# adb_converter.net
KiCad netlist of a schematic drawn in EAGLE
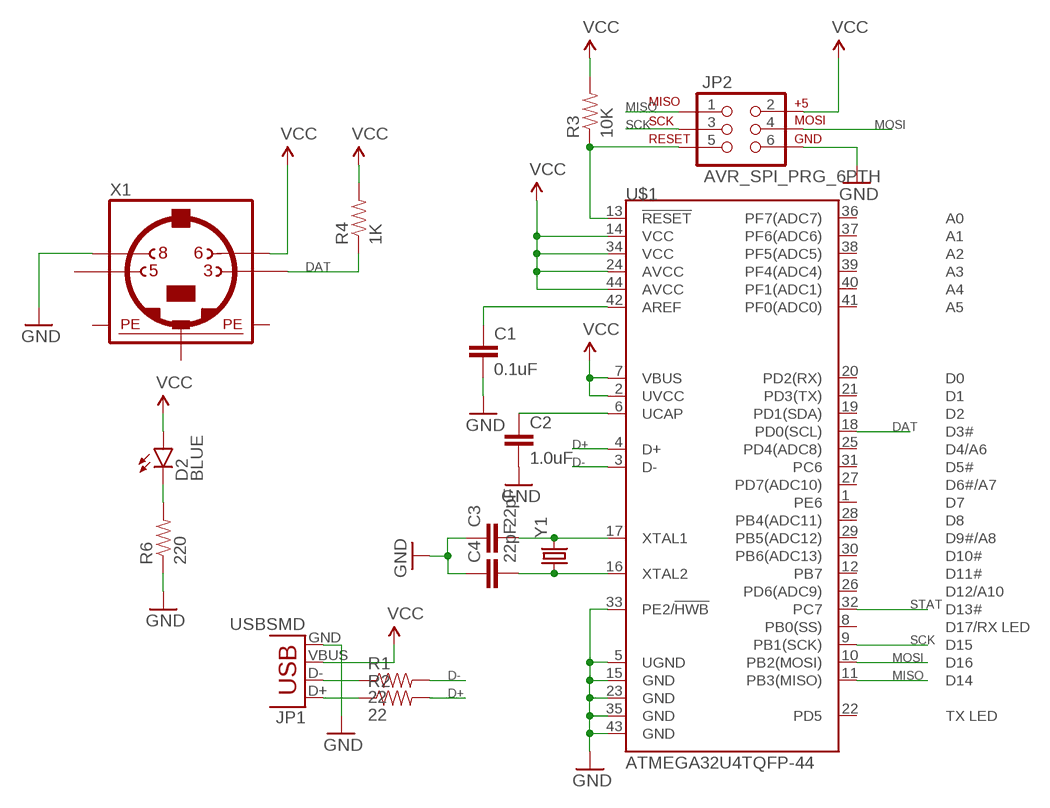
[diagram p0: schematic, sheet 1]

(export (version "E")
  (design (tool "Eeschema 10.0.6"))
  (components
    (comp (ref "C1")
      (value "0.1uF")
      (footprint "eagle-import:0603-CAP")
      (libsource (lib "eagle-import") (part "0.1UF-25V-5%(0603)"))
    )
    (comp (ref "C2")
      (value "1.0uF")
      (footprint "eagle-import:0603-CAP")
      (libsource (lib "eagle-import") (part "1.0UF-16V-10%(0603)"))
    )
    (comp (ref "C3")
      (value "22pF")
      (footprint "eagle-import:0603-CAP")
      (libsource (lib "eagle-import") (part "22PF-50V-5%(0603)"))
    )
    (comp (ref "C4")
      (value "22pF")
      (footprint "eagle-import:0603-CAP")
      (libsource (lib "eagle-import") (part "22PF-50V-5%(0603)"))
    )
    (comp (ref "D2")
      (value "BLUE")
      (footprint "eagle-import:LED-0603")
      (libsource (lib "eagle-import") (part "LED-BLUE0603"))
    )
    (comp (ref "JP1")
      (value "USBSMD")
      (footprint "eagle-import:USB-MINIB")
      (libsource (lib "eagle-import") (part "USBSMD"))
    )
    (comp (ref "JP2")
      (value "AVR_SPI_PRG_6PTH")
      (footprint "eagle-import:2X3")
      (libsource (lib "eagle-import") (part "AVR_SPI_PRG_6PTH"))
    )
    (comp (ref "R1")
      (value "22")
      (footprint "eagle-import:0603-RES")
      (libsource (lib "eagle-import") (part "22OHM1/10W1%(0603)"))
    )
    (comp (ref "R2")
      (value "22")
      (footprint "eagle-import:0603-RES")
      (libsource (lib "eagle-import") (part "22OHM1/10W1%(0603)"))
    )
    (comp (ref "R3")
      (value "10K")
      (footprint "eagle-import:0603-RES")
      (libsource (lib "eagle-import") (part "10KOHM-1/10W-1%(0603)0603"))
    )
    (comp (ref "R4")
      (value "1K")
      (footprint "eagle-import:0603-RES")
      (libsource (lib "eagle-import") (part "1KOHM-1/10W-1%(0603)"))
    )
    (comp (ref "R6")
      (value "220")
      (footprint "eagle-import:0603-RES")
      (libsource (lib "eagle-import") (part "220OHM-1/10W-1%(0603)"))
    )
    (comp (ref "U$1")
      (value "ATMEGA32U4TQFP-44")
      (footprint "eagle-import:TQFP44")
      (libsource (lib "eagle-import") (part "ATMEGA32U4TQFP-44"))
    )
    (comp (ref "X1")
      (value "MINI_DIN_4")
      (footprint "eagle-import:M_DIN4")
      (libsource (lib "eagle-import") (part "MINI_DIN_4"))
    )
    (comp (ref "Y1")
      (value "CRYSTALHC49US")
      (footprint "eagle-import:HC49US")
      (libsource (lib "eagle-import") (part "CRYSTALHC49US"))
    )
  )
  (nets
    (net (code "1") (name "/D+") (class "Default")
      (node (ref "R2") (pin "2") (pinfunction "2_2") (pintype "passive"))
      (node (ref "U$1") (pin "4") (pinfunction "D+_4") (pintype "bidirectional"))
    )
    (net (code "2") (name "/D-") (class "Default")
      (node (ref "R1") (pin "2") (pinfunction "2_2") (pintype "passive"))
      (node (ref "U$1") (pin "3") (pinfunction "D-_3") (pintype "bidirectional"))
    )
    (net (code "3") (name "/DAT") (class "Default")
      (node (ref "R4") (pin "1") (pinfunction "1_1") (pintype "passive"))
      (node (ref "U$1") (pin "18") (pinfunction "PD0(SCL)_18") (pintype "bidirectional"))
      (node (ref "X1") (pin "3") (pinfunction "3_3") (pintype "passive"))
    )
    (net (code "4") (name "/MISO") (class "Default")
      (node (ref "JP2") (pin "1") (pinfunction "1_1") (pintype "passive"))
      (node (ref "U$1") (pin "11") (pinfunction "PB3(MISO)_11") (pintype "bidirectional"))
    )
    (net (code "5") (name "/MOSI") (class "Default")
      (node (ref "JP2") (pin "4") (pinfunction "4_4") (pintype "passive"))
      (node (ref "U$1") (pin "10") (pinfunction "PB2(MOSI)_10") (pintype "bidirectional"))
    )
    (net (code "6") (name "/PE1") (class "Default")
      (node (ref "X1") (pin "SH1") (pinfunction "PE1_SH1") (pintype "power_in"))
    )
    (net (code "7") (name "/PE2") (class "Default")
      (node (ref "X1") (pin "SH2") (pinfunction "PE2_SH2") (pintype "power_in"))
    )
    (net (code "8") (name "/PE3") (class "Default")
      (node (ref "X1") (pin "SH3") (pinfunction "PE3_SH3") (pintype "power_in"))
    )
    (net (code "9") (name "/SCK") (class "Default")
      (node (ref "JP2") (pin "3") (pinfunction "3_3") (pintype "passive"))
      (node (ref "U$1") (pin "9") (pinfunction "PB1(SCK)_9") (pintype "bidirectional"))
    )
    (net (code "10") (name "/STAT") (class "Default")
      (node (ref "U$1") (pin "32") (pinfunction "PC7_32") (pintype "bidirectional"))
    )
    (net (code "11") (name "GND") (class "Default")
      (node (ref "C1") (pin "2") (pinfunction "2_2") (pintype "passive"))
      (node (ref "C2") (pin "2") (pinfunction "2_2") (pintype "passive"))
      (node (ref "C3") (pin "1") (pinfunction "1_1") (pintype "passive"))
      (node (ref "C4") (pin "1") (pinfunction "1_1") (pintype "passive"))
      (node (ref "JP1") (pin "GND") (pinfunction "GND_GND") (pintype "bidirectional"))
      (node (ref "JP2") (pin "6") (pinfunction "6_6") (pintype "passive"))
      (node (ref "R6") (pin "1") (pinfunction "1_1") (pintype "passive"))
      (node (ref "U$1") (pin "15") (pinfunction "GND_15") (pintype "bidirectional"))
      (node (ref "U$1") (pin "23") (pinfunction "GND_23") (pintype "bidirectional"))
      (node (ref "U$1") (pin "33") (pinfunction "PE2/~{HWB}_33") (pintype "bidirectional"))
      (node (ref "U$1") (pin "35") (pinfunction "GND_35") (pintype "bidirectional"))
      (node (ref "U$1") (pin "43") (pinfunction "GND_43") (pintype "bidirectional"))
      (node (ref "U$1") (pin "5") (pinfunction "UGND_5") (pintype "bidirectional"))
      (node (ref "X1") (pin "8") (pinfunction "8_8") (pintype "passive"))
    )
    (net (code "12") (name "Net-(D2-PadC)") (class "Default")
      (node (ref "D2") (pin "C") (pinfunction "C_C") (pintype "passive"))
      (node (ref "R6") (pin "2") (pinfunction "2_2") (pintype "passive"))
    )
    (net (code "13") (name "Net-(JP1-PadD+)") (class "Default")
      (node (ref "JP1") (pin "D+") (pinfunction "D+_D+") (pintype "bidirectional"))
      (node (ref "R2") (pin "1") (pinfunction "1_1") (pintype "passive"))
    )
    (net (code "14") (name "Net-(JP1-PadD-)") (class "Default")
      (node (ref "JP1") (pin "D-") (pinfunction "D-_D-") (pintype "bidirectional"))
      (node (ref "R1") (pin "1") (pinfunction "1_1") (pintype "passive"))
    )
    (net (code "15") (name "Net-(U$1-AREF)") (class "Default")
      (node (ref "C1") (pin "1") (pinfunction "1_1") (pintype "passive"))
      (node (ref "U$1") (pin "42") (pinfunction "AREF_42") (pintype "bidirectional"))
    )
    (net (code "16") (name "Net-(U$1-UCAP)") (class "Default")
      (node (ref "C2") (pin "1") (pinfunction "1_1") (pintype "passive"))
      (node (ref "U$1") (pin "6") (pinfunction "UCAP_6") (pintype "bidirectional"))
    )
    (net (code "17") (name "Net-(U$1-XTAL1)") (class "Default")
      (node (ref "C3") (pin "2") (pinfunction "2_2") (pintype "passive"))
      (node (ref "U$1") (pin "17") (pinfunction "XTAL1_17") (pintype "bidirectional"))
      (node (ref "Y1") (pin "2") (pinfunction "2_2") (pintype "passive"))
    )
    (net (code "18") (name "Net-(U$1-XTAL2)") (class "Default")
      (node (ref "C4") (pin "2") (pinfunction "2_2") (pintype "passive"))
      (node (ref "U$1") (pin "16") (pinfunction "XTAL2_16") (pintype "bidirectional"))
      (node (ref "Y1") (pin "1") (pinfunction "1_1") (pintype "passive"))
    )
    (net (code "19") (name "Net-(U$1-~{RESET})") (class "Default")
      (node (ref "JP2") (pin "5") (pinfunction "5_5") (pintype "passive"))
      (node (ref "R3") (pin "1") (pinfunction "1_1") (pintype "passive"))
      (node (ref "U$1") (pin "13") (pinfunction "~{RESET}_13") (pintype "bidirectional"))
    )
    (net (code "20") (name "VCC") (class "Default")
      (node (ref "D2") (pin "A") (pinfunction "A_A") (pintype "passive"))
      (node (ref "JP1") (pin "VBUS") (pinfunction "VBUS_VBUS") (pintype "bidirectional"))
      (node (ref "JP2") (pin "2") (pinfunction "2_2") (pintype "passive"))
      (node (ref "R3") (pin "2") (pinfunction "2_2") (pintype "passive"))
      (node (ref "R4") (pin "2") (pinfunction "2_2") (pintype "passive"))
      (node (ref "U$1") (pin "14") (pinfunction "VCC_14") (pintype "bidirectional"))
      (node (ref "U$1") (pin "2") (pinfunction "UVCC_2") (pintype "bidirectional"))
      (node (ref "U$1") (pin "24") (pinfunction "AVCC_24") (pintype "bidirectional"))
      (node (ref "U$1") (pin "34") (pinfunction "VCC_34") (pintype "bidirectional"))
      (node (ref "U$1") (pin "44") (pinfunction "AVCC_44") (pintype "bidirectional"))
      (node (ref "U$1") (pin "7") (pinfunction "VBUS_7") (pintype "bidirectional"))
      (node (ref "X1") (pin "6") (pinfunction "6_6") (pintype "passive"))
    )
    (net (code "21") (name "unconnected-(U$1-PB0(SS)-Pad8)") (class "Default")
      (node (ref "U$1") (pin "8") (pinfunction "PB0(SS)_8") (pintype "bidirectional"))
    )
    (net (code "22") (name "unconnected-(U$1-PB4(ADC11)-Pad28)") (class "Default")
      (node (ref "U$1") (pin "28") (pinfunction "PB4(ADC11)_28") (pintype "bidirectional"))
    )
    (net (code "23") (name "unconnected-(U$1-PB5(ADC12)-Pad29)") (class "Default")
      (node (ref "U$1") (pin "29") (pinfunction "PB5(ADC12)_29") (pintype "bidirectional"))
    )
    (net (code "24") (name "unconnected-(U$1-PB6(ADC13)-Pad30)") (class "Default")
      (node (ref "U$1") (pin "30") (pinfunction "PB6(ADC13)_30") (pintype "bidirectional"))
    )
    (net (code "25") (name "unconnected-(U$1-PB7-Pad12)") (class "Default")
      (node (ref "U$1") (pin "12") (pinfunction "PB7_12") (pintype "bidirectional"))
    )
    (net (code "26") (name "unconnected-(U$1-PC6-Pad31)") (class "Default")
      (node (ref "U$1") (pin "31") (pinfunction "PC6_31") (pintype "bidirectional"))
    )
    (net (code "27") (name "unconnected-(U$1-PD1(SDA)-Pad19)") (class "Default")
      (node (ref "U$1") (pin "19") (pinfunction "PD1(SDA)_19") (pintype "bidirectional"))
    )
    (net (code "28") (name "unconnected-(U$1-PD2(RX)-Pad20)") (class "Default")
      (node (ref "U$1") (pin "20") (pinfunction "PD2(RX)_20") (pintype "bidirectional"))
    )
    (net (code "29") (name "unconnected-(U$1-PD3(TX)-Pad21)") (class "Default")
      (node (ref "U$1") (pin "21") (pinfunction "PD3(TX)_21") (pintype "bidirectional"))
    )
    (net (code "30") (name "unconnected-(U$1-PD4(ADC8)-Pad25)") (class "Default")
      (node (ref "U$1") (pin "25") (pinfunction "PD4(ADC8)_25") (pintype "bidirectional"))
    )
    (net (code "31") (name "unconnected-(U$1-PD5-Pad22)") (class "Default")
      (node (ref "U$1") (pin "22") (pinfunction "PD5_22") (pintype "bidirectional"))
    )
    (net (code "32") (name "unconnected-(U$1-PD6(ADC9)-Pad26)") (class "Default")
      (node (ref "U$1") (pin "26") (pinfunction "PD6(ADC9)_26") (pintype "bidirectional"))
    )
    (net (code "33") (name "unconnected-(U$1-PD7(ADC10)-Pad27)") (class "Default")
      (node (ref "U$1") (pin "27") (pinfunction "PD7(ADC10)_27") (pintype "bidirectional"))
    )
    (net (code "34") (name "unconnected-(U$1-PE6-Pad1)") (class "Default")
      (node (ref "U$1") (pin "1") (pinfunction "PE6_1") (pintype "bidirectional"))
    )
    (net (code "35") (name "unconnected-(U$1-PF0(ADC0)-Pad41)") (class "Default")
      (node (ref "U$1") (pin "41") (pinfunction "PF0(ADC0)_41") (pintype "bidirectional"))
    )
    (net (code "36") (name "unconnected-(U$1-PF1(ADC1)-Pad40)") (class "Default")
      (node (ref "U$1") (pin "40") (pinfunction "PF1(ADC1)_40") (pintype "bidirectional"))
    )
    (net (code "37") (name "unconnected-(U$1-PF4(ADC4)-Pad39)") (class "Default")
      (node (ref "U$1") (pin "39") (pinfunction "PF4(ADC4)_39") (pintype "bidirectional"))
    )
    (net (code "38") (name "unconnected-(U$1-PF5(ADC5)-Pad38)") (class "Default")
      (node (ref "U$1") (pin "38") (pinfunction "PF5(ADC5)_38") (pintype "bidirectional"))
    )
    (net (code "39") (name "unconnected-(U$1-PF6(ADC6)-Pad37)") (class "Default")
      (node (ref "U$1") (pin "37") (pinfunction "PF6(ADC6)_37") (pintype "bidirectional"))
    )
    (net (code "40") (name "unconnected-(U$1-PF7(ADC7)-Pad36)") (class "Default")
      (node (ref "U$1") (pin "36") (pinfunction "PF7(ADC7)_36") (pintype "bidirectional"))
    )
    (net (code "41") (name "unconnected-(X1-Pad5)") (class "Default")
      (node (ref "X1") (pin "5") (pinfunction "5_5") (pintype "passive"))
    )
  )
)
